# 3_CAN.net
KiCad netlist of a schematic drawn in Altium Designer
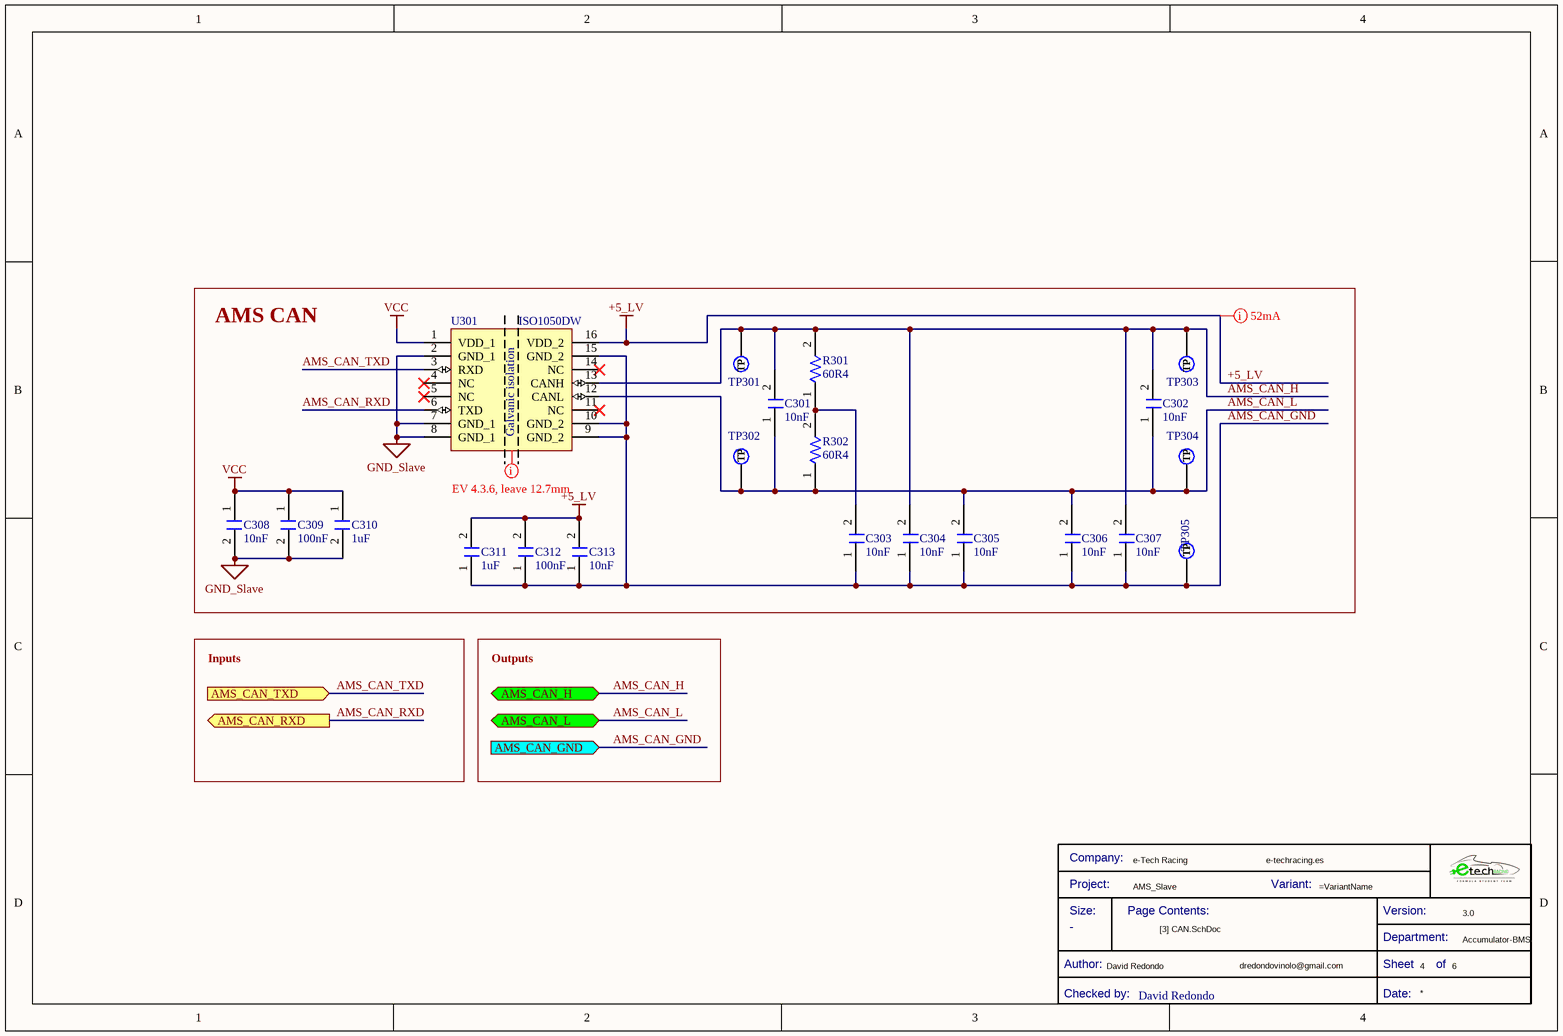
[diagram p0: [3] CAN.SchDoc]

(export (version "E")
  (design (tool "Eeschema 10.0.6"))
  (components
    (comp (ref "*")
      (value "Title Block_template")
      (description "Standard Title Block")
      (fields (field (name "SIZE") "-"))
      (libsource (lib "e-Tech_Racing") (part "Title Block_template"))
    )
    (comp (ref "C301")
      (value "885012207092")
      (footprint "C0805FNPC-R")
      (description "Cap, 0.01ΜF, 50V, 10%, X7R, 0805")
      (fields
        (field (name "TOLERANCE") "10%")
        (field (name "CAPACITANCE") "10nF")
        (field (name ".CREATOR") "DR")
      )
      (libsource (lib "Passives") (part "C10n-50V-0805FNPC-X7R"))
    )
    (comp (ref "C302")
      (value "885012207092")
      (footprint "C0805FNPC-R")
      (description "Cap, 0.01ΜF, 50V, 10%, X7R, 0805")
      (fields
        (field (name "TOLERANCE") "10%")
        (field (name "CAPACITANCE") "10nF")
        (field (name ".CREATOR") "DR")
      )
      (libsource (lib "Passives") (part "C10n-50V-0805FNPC-X7R"))
    )
    (comp (ref "C303")
      (value "885012207092")
      (footprint "C0805FNPC-R")
      (description "Cap, 0.01ΜF, 50V, 10%, X7R, 0805")
      (fields
        (field (name "TOLERANCE") "10%")
        (field (name "CAPACITANCE") "10nF")
        (field (name ".CREATOR") "DR")
      )
      (libsource (lib "Passives") (part "C10n-50V-0805FNPC-X7R"))
    )
    (comp (ref "C304")
      (value "885012207092")
      (footprint "C0805FNPC-R")
      (description "Cap, 0.01ΜF, 50V, 10%, X7R, 0805")
      (fields
        (field (name "TOLERANCE") "10%")
        (field (name "CAPACITANCE") "10nF")
        (field (name ".CREATOR") "DR")
      )
      (libsource (lib "Passives") (part "C10n-50V-0805FNPC-X7R"))
    )
    (comp (ref "C305")
      (value "885012207092")
      (footprint "C0805FNPC-R")
      (description "Cap, 0.01ΜF, 50V, 10%, X7R, 0805")
      (fields
        (field (name "TOLERANCE") "10%")
        (field (name "CAPACITANCE") "10nF")
        (field (name ".CREATOR") "DR")
      )
      (libsource (lib "Passives") (part "C10n-50V-0805FNPC-X7R"))
    )
    (comp (ref "C306")
      (value "885012207092")
      (footprint "C0805FNPC-R")
      (description "Cap, 0.01ΜF, 50V, 10%, X7R, 0805")
      (fields
        (field (name "TOLERANCE") "10%")
        (field (name "CAPACITANCE") "10nF")
        (field (name ".CREATOR") "DR")
      )
      (libsource (lib "Passives") (part "C10n-50V-0805FNPC-X7R"))
    )
    (comp (ref "C307")
      (value "885012207092")
      (footprint "C0805FNPC-R")
      (description "Cap, 0.01ΜF, 50V, 10%, X7R, 0805")
      (fields
        (field (name "TOLERANCE") "10%")
        (field (name "CAPACITANCE") "10nF")
        (field (name ".CREATOR") "DR")
      )
      (libsource (lib "Passives") (part "C10n-50V-0805FNPC-X7R"))
    )
    (comp (ref "C308")
      (value "885012207092")
      (footprint "C0805FNPC-R")
      (description "Cap, 0.01ΜF, 50V, 10%, X7R, 0805")
      (fields
        (field (name "TOLERANCE") "10%")
        (field (name "CAPACITANCE") "10nF")
        (field (name ".CREATOR") "DR")
      )
      (libsource (lib "Passives") (part "C10n-50V-0805FNPC-X7R"))
    )
    (comp (ref "C309")
      (value "885012207098")
      (footprint "C0805FNPC-R")
      (description "Cap, 0.1ΜF, 50V, 10%, X7R, 0805")
      (fields
        (field (name "TOLERANCE") "10%")
        (field (name "CAPACITANCE") "100nF")
        (field (name ".CREATOR") "DR")
      )
      (libsource (lib "Passives") (part "C100n-50V-0805FNPC-X7R"))
    )
    (comp (ref "C310")
      (value "885012207103")
      (footprint "C0805FNPC-R")
      (fields
        (field (name "TOLERANCE") "10%")
        (field (name "CAPACITANCE") "1uF")
        (field (name ".CREATOR") "GP")
      )
      (libsource (lib "Passives") (part "C1u-50V-0805FNPC-X7R"))
    )
    (comp (ref "C311")
      (value "885012207103")
      (footprint "C0805FNPC-R")
      (fields
        (field (name "TOLERANCE") "10%")
        (field (name "CAPACITANCE") "1uF")
        (field (name ".CREATOR") "GP")
      )
      (libsource (lib "Passives") (part "C1u-50V-0805FNPC-X7R"))
    )
    (comp (ref "C312")
      (value "885012207098")
      (footprint "C0805FNPC-R")
      (description "Cap, 0.1ΜF, 50V, 10%, X7R, 0805")
      (fields
        (field (name "TOLERANCE") "10%")
        (field (name "CAPACITANCE") "100nF")
        (field (name ".CREATOR") "DR")
      )
      (libsource (lib "Passives") (part "C100n-50V-0805FNPC-X7R"))
    )
    (comp (ref "C313")
      (value "885012207092")
      (footprint "C0805FNPC-R")
      (description "Cap, 0.01ΜF, 50V, 10%, X7R, 0805")
      (fields
        (field (name "TOLERANCE") "10%")
        (field (name "CAPACITANCE") "10nF")
        (field (name ".CREATOR") "DR")
      )
      (libsource (lib "Passives") (part "C10n-50V-0805FNPC-X7R"))
    )
    (comp (ref "R301")
      (value "60R4")
      (footprint "R0805FTK")
      (description "Res Thin Film 0805 60.4 Ohm 0.1% 1/8W ±25ppm/°C Molded SMD SMD Punched Carrier T/R")
      (fields
        (field (name "TOLERANCE") "0.1%")
        (field (name "Comment") "R60-0805FTN")
        (field (name ".CREATOR") "DR")
      )
      (libsource (lib "Passives") (part "R60-0805FTN"))
    )
    (comp (ref "R302")
      (value "60R4")
      (footprint "R0805FTK")
      (description "Res Thin Film 0805 60.4 Ohm 0.1% 1/8W ±25ppm/°C Molded SMD SMD Punched Carrier T/R")
      (fields
        (field (name "TOLERANCE") "0.1%")
        (field (name "Comment") "R60-0805FTN")
        (field (name ".CREATOR") "DR")
      )
      (libsource (lib "Passives") (part "R60-0805FTN"))
    )
    (comp (ref "TP301")
      (value "TestPoint")
      (footprint "TestPoint")
      (description "Test Point 1x1 mm")
      (fields (field (name ".CREATOR") "GP") (field (name ".PCBCHECK") "GP") (field (name ".SCHCHECK") "GP"))
      (libsource (lib "e-Tech_Racing") (part "TestPoint"))
    )
    (comp (ref "TP302")
      (value "TestPoint")
      (footprint "TestPoint")
      (description "Test Point 1x1 mm")
      (fields (field (name ".CREATOR") "GP") (field (name ".PCBCHECK") "GP") (field (name ".SCHCHECK") "GP"))
      (libsource (lib "e-Tech_Racing") (part "TestPoint"))
    )
    (comp (ref "TP303")
      (value "TestPoint")
      (footprint "TestPoint")
      (description "Test Point 1x1 mm")
      (fields (field (name ".CREATOR") "GP") (field (name ".PCBCHECK") "GP") (field (name ".SCHCHECK") "GP"))
      (libsource (lib "e-Tech_Racing") (part "TestPoint"))
    )
    (comp (ref "TP304")
      (value "TestPoint")
      (footprint "TestPoint")
      (description "Test Point 1x1 mm")
      (fields (field (name ".CREATOR") "GP") (field (name ".PCBCHECK") "GP") (field (name ".SCHCHECK") "GP"))
      (libsource (lib "e-Tech_Racing") (part "TestPoint"))
    )
    (comp (ref "TP305")
      (value "TestPoint")
      (footprint "TestPoint")
      (description "Test Point 1x1 mm")
      (fields (field (name ".CREATOR") "GP") (field (name ".PCBCHECK") "GP") (field (name ".SCHCHECK") "GP"))
      (libsource (lib "e-Tech_Racing") (part "TestPoint"))
    )
    (comp (ref "U301")
      (value "ISO1050DW")
      (footprint "TRANSCEIVER_CAN_SOIC16")
      (description "Isolated 5-V CAN transceiver 16-SOIC -55 to 105")
      (fields (field (name "SUPPLIER PART NUMBER 1") "ISO1050DW") (field (name ".CREATOR") "DR"))
      (libsource (lib "Integrated circuits") (part "Transceiver_CAN_ISO1050"))
    )
  )
  (nets
    (net (code "1") (name "+5_LV") (class "Default")
      (node (ref "C311") (pin "2") (pinfunction "2_2") (pintype "passive"))
      (node (ref "C312") (pin "2") (pinfunction "2_2") (pintype "passive"))
      (node (ref "C313") (pin "2") (pinfunction "2_2") (pintype "passive"))
      (node (ref "U301") (pin "16") (pinfunction "VDD_2_16") (pintype "passive"))
    )
    (net (code "2") (name "/AMS_CAN_GND") (class "Default")
      (node (ref "C303") (pin "1") (pinfunction "1_1") (pintype "passive"))
      (node (ref "C304") (pin "1") (pinfunction "1_1") (pintype "passive"))
      (node (ref "C305") (pin "1") (pinfunction "1_1") (pintype "passive"))
      (node (ref "C306") (pin "1") (pinfunction "1_1") (pintype "passive"))
      (node (ref "C307") (pin "1") (pinfunction "1_1") (pintype "passive"))
      (node (ref "C311") (pin "1") (pinfunction "1_1") (pintype "passive"))
      (node (ref "C312") (pin "1") (pinfunction "1_1") (pintype "passive"))
      (node (ref "C313") (pin "1") (pinfunction "1_1") (pintype "passive"))
      (node (ref "TP305") (pin "1") (pinfunction "TP_1") (pintype "passive"))
      (node (ref "U301") (pin "10") (pinfunction "GND_2_10") (pintype "passive"))
      (node (ref "U301") (pin "15") (pinfunction "GND_2_15") (pintype "passive"))
      (node (ref "U301") (pin "9") (pinfunction "GND_2_9") (pintype "passive"))
    )
    (net (code "3") (name "/AMS_CAN_H") (class "Default")
      (node (ref "C301") (pin "2") (pinfunction "2_2") (pintype "passive"))
      (node (ref "C302") (pin "2") (pinfunction "2_2") (pintype "passive"))
      (node (ref "C304") (pin "2") (pinfunction "2_2") (pintype "passive"))
      (node (ref "C307") (pin "2") (pinfunction "2_2") (pintype "passive"))
      (node (ref "R301") (pin "2") (pinfunction "2_2") (pintype "passive"))
      (node (ref "TP301") (pin "1") (pinfunction "TP_1") (pintype "passive"))
      (node (ref "TP303") (pin "1") (pinfunction "TP_1") (pintype "passive"))
      (node (ref "U301") (pin "13") (pinfunction "CANH_13") (pintype "bidirectional"))
    )
    (net (code "4") (name "/AMS_CAN_L") (class "Default")
      (node (ref "C301") (pin "1") (pinfunction "1_1") (pintype "passive"))
      (node (ref "C302") (pin "1") (pinfunction "1_1") (pintype "passive"))
      (node (ref "C305") (pin "2") (pinfunction "2_2") (pintype "passive"))
      (node (ref "C306") (pin "2") (pinfunction "2_2") (pintype "passive"))
      (node (ref "R302") (pin "1") (pinfunction "1_1") (pintype "passive"))
      (node (ref "TP302") (pin "1") (pinfunction "TP_1") (pintype "passive"))
      (node (ref "TP304") (pin "1") (pinfunction "TP_1") (pintype "passive"))
      (node (ref "U301") (pin "12") (pinfunction "CANL_12") (pintype "bidirectional"))
    )
    (net (code "5") (name "/AMS_CAN_RXD") (class "Default")
      (node (ref "U301") (pin "6") (pinfunction "TXD_6") (pintype "bidirectional"))
    )
    (net (code "6") (name "/AMS_CAN_TXD") (class "Default")
      (node (ref "U301") (pin "3") (pinfunction "RXD_3") (pintype "bidirectional"))
    )
    (net (code "7") (name "GND_Slave") (class "Default")
      (node (ref "C308") (pin "2") (pinfunction "2_2") (pintype "passive"))
      (node (ref "C309") (pin "2") (pinfunction "2_2") (pintype "passive"))
      (node (ref "C310") (pin "2") (pinfunction "2_2") (pintype "passive"))
      (node (ref "U301") (pin "2") (pinfunction "GND_1_2") (pintype "power_in"))
      (node (ref "U301") (pin "7") (pinfunction "GND_1_7") (pintype "passive"))
      (node (ref "U301") (pin "8") (pinfunction "GND_1_8") (pintype "passive"))
    )
    (net (code "8") (name "Net-(C303-Pad2)") (class "Default")
      (node (ref "C303") (pin "2") (pinfunction "2_2") (pintype "passive"))
      (node (ref "R301") (pin "1") (pinfunction "1_1") (pintype "passive"))
      (node (ref "R302") (pin "2") (pinfunction "2_2") (pintype "passive"))
    )
    (net (code "9") (name "VCC") (class "Default")
      (node (ref "C308") (pin "1") (pinfunction "1_1") (pintype "passive"))
      (node (ref "C309") (pin "1") (pinfunction "1_1") (pintype "passive"))
      (node (ref "C310") (pin "1") (pinfunction "1_1") (pintype "passive"))
      (node (ref "U301") (pin "1") (pinfunction "VDD_1_1") (pintype "open_collector"))
    )
    (net (code "10") (name "unconnected-(U301-NC-Pad4)") (class "Default")
      (node (ref "U301") (pin "4") (pinfunction "NC_4") (pintype "open_emitter+no_connect"))
    )
    (net (code "11") (name "unconnected-(U301-NC-Pad5)") (class "Default")
      (node (ref "U301") (pin "5") (pinfunction "NC_5") (pintype "passive+no_connect"))
    )
    (net (code "12") (name "unconnected-(U301-NC-Pad11)") (class "Default")
      (node (ref "U301") (pin "11") (pinfunction "NC_11") (pintype "passive+no_connect"))
    )
    (net (code "13") (name "unconnected-(U301-NC-Pad14)") (class "Default")
      (node (ref "U301") (pin "14") (pinfunction "NC_14") (pintype "open_collector+no_connect"))
    )
  )
)
